# 5VAC-DC.net
KiCad netlist of a schematic drawn in EAGLE
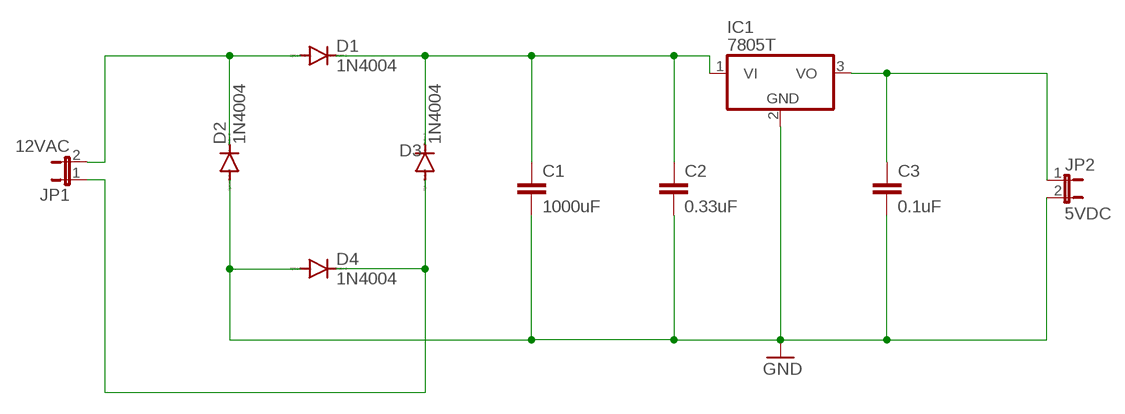
[diagram p0: schematic, sheet 1]

(export (version "E")
  (design (tool "Eeschema 10.0.6"))
  (components
    (comp (ref "C1")
      (value "1000uF")
      (footprint "eagle-import:C2.5-3")
      (libsource (lib "eagle-import") (part "C2,5-3"))
    )
    (comp (ref "C2")
      (value "0.33uF")
      (footprint "eagle-import:C2.5-3")
      (libsource (lib "eagle-import") (part "C2,5-3"))
    )
    (comp (ref "C3")
      (value "0.1uF")
      (footprint "eagle-import:C2.5-3")
      (libsource (lib "eagle-import") (part "C2,5-3"))
    )
    (comp (ref "D1")
      (value "1N4004")
      (footprint "eagle-import:DO41-10")
      (libsource (lib "eagle-import") (part "1N4004"))
    )
    (comp (ref "D2")
      (value "1N4004")
      (footprint "eagle-import:DO41-10")
      (libsource (lib "eagle-import") (part "1N4004"))
    )
    (comp (ref "D3")
      (value "1N4004")
      (footprint "eagle-import:DO41-10")
      (libsource (lib "eagle-import") (part "1N4004"))
    )
    (comp (ref "D4")
      (value "1N4004")
      (footprint "eagle-import:DO41-10")
      (libsource (lib "eagle-import") (part "1N4004"))
    )
    (comp (ref "IC1")
      (value "7805T")
      (footprint "eagle-import:TO220H")
      (libsource (lib "eagle-import") (part "78T05"))
    )
    (comp (ref "JP1")
      (value "12VAC")
      (footprint "eagle-import:JP1")
      (libsource (lib "eagle-import") (part "JP1E"))
    )
    (comp (ref "JP2")
      (value "5VDC")
      (footprint "eagle-import:JP1")
      (libsource (lib "eagle-import") (part "JP1E"))
    )
  )
  (nets
    (net (code "1") (name "GND") (class "Default")
      (node (ref "C1") (pin "2") (pinfunction "2_2") (pintype "passive"))
      (node (ref "C2") (pin "2") (pinfunction "2_2") (pintype "passive"))
      (node (ref "C3") (pin "2") (pinfunction "2_2") (pintype "passive"))
      (node (ref "D2") (pin "A") (pinfunction "A_A") (pintype "passive"))
      (node (ref "D4") (pin "A") (pinfunction "A_A") (pintype "passive"))
      (node (ref "IC1") (pin "2") (pinfunction "GND_2") (pintype "passive"))
      (node (ref "JP2") (pin "2") (pinfunction "2_2") (pintype "passive"))
    )
    (net (code "2") (name "Net-(D1-PadA)") (class "Default")
      (node (ref "D1") (pin "A") (pinfunction "A_A") (pintype "passive"))
      (node (ref "D2") (pin "C") (pinfunction "C_C") (pintype "passive"))
      (node (ref "JP1") (pin "2") (pinfunction "2_2") (pintype "passive"))
    )
    (net (code "3") (name "Net-(D3-PadA)") (class "Default")
      (node (ref "D3") (pin "A") (pinfunction "A_A") (pintype "passive"))
      (node (ref "D4") (pin "C") (pinfunction "C_C") (pintype "passive"))
      (node (ref "JP1") (pin "1") (pinfunction "1_1") (pintype "passive"))
    )
    (net (code "4") (name "Net-(IC1-VI)") (class "Default")
      (node (ref "C1") (pin "1") (pinfunction "1_1") (pintype "passive"))
      (node (ref "C2") (pin "1") (pinfunction "1_1") (pintype "passive"))
      (node (ref "D1") (pin "C") (pinfunction "C_C") (pintype "passive"))
      (node (ref "D3") (pin "C") (pinfunction "C_C") (pintype "passive"))
      (node (ref "IC1") (pin "1") (pinfunction "VI_1") (pintype "input"))
    )
    (net (code "5") (name "Net-(IC1-VO)") (class "Default")
      (node (ref "C3") (pin "1") (pinfunction "1_1") (pintype "passive"))
      (node (ref "IC1") (pin "3") (pinfunction "VO_3") (pintype "passive"))
      (node (ref "JP2") (pin "1") (pinfunction "1_1") (pintype "passive"))
    )
  )
)
